# EconetTerminator.net
KiCad netlist of a schematic drawn in Altium Designer
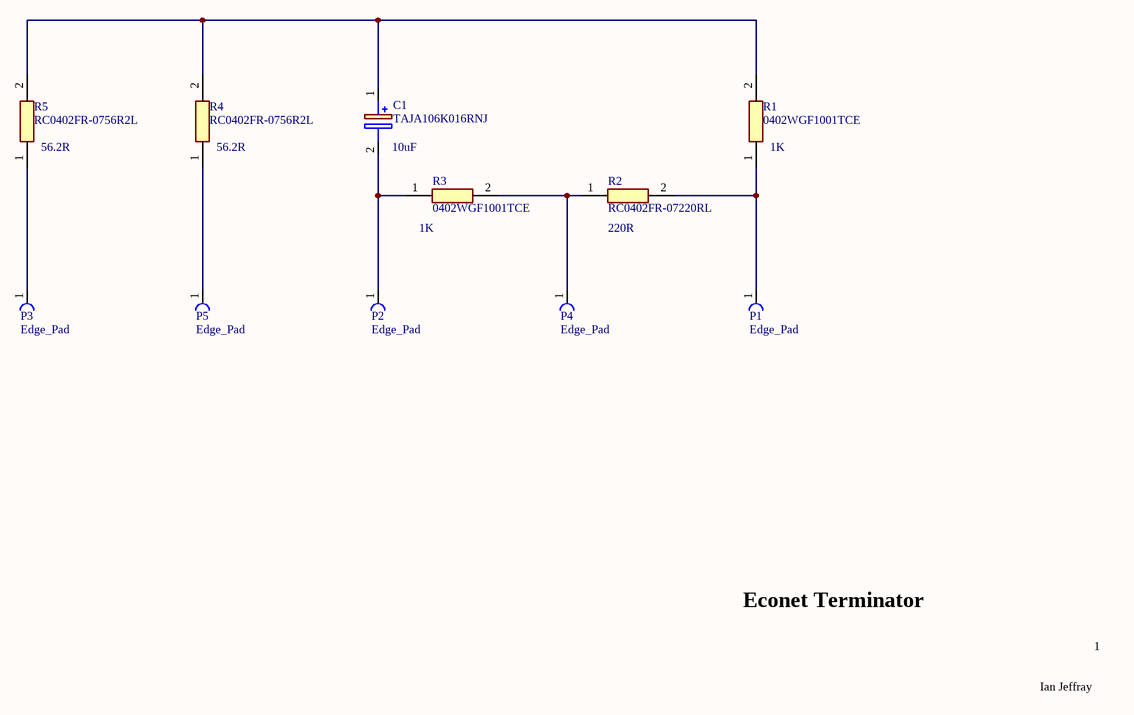
[diagram p0: EconetTerminator.SchDoc]

(export (version "E")
  (design (tool "Eeschema 10.0.6"))
  (components
    (comp (ref "C1")
      (value "TAJA106K016RNJ")
      (footprint "SamacSys:CAPPM3216X180N")
      (description "10uF Tantalum")
      (fields (field (name "MOUSER PART NUMBER") "581-TAJA106K016R") (field (name "ALTIUM_VALUE") "10uF"))
      (libsource (lib "*") (part "TAJA106K016RNJ"))
    )
    (comp (ref "P1")
      (value "Edge_Pad")
      (footprint "CONS_PAD")
      (description "Edge Pad")
      (libsource (lib "EconetTerminator") (part "Edge_Pad"))
    )
    (comp (ref "P2")
      (value "Edge_Pad")
      (footprint "CONS_PAD")
      (description "Edge Pad")
      (libsource (lib "EconetTerminator") (part "Edge_Pad"))
    )
    (comp (ref "P3")
      (value "Edge_Pad")
      (footprint "CONS_PAD")
      (description "Edge Pad")
      (libsource (lib "EconetTerminator") (part "Edge_Pad"))
    )
    (comp (ref "P4")
      (value "Edge_Pad")
      (footprint "CONS_PAD")
      (description "Edge Pad")
      (libsource (lib "EconetTerminator") (part "Edge_Pad"))
    )
    (comp (ref "P5")
      (value "Edge_Pad")
      (footprint "CONS_PAD")
      (description "Edge Pad")
      (libsource (lib "EconetTerminator") (part "Edge_Pad"))
    )
    (comp (ref "R1")
      (value "0402WGF1001TCE")
      (footprint "SamacSys:RESC1005X40N")
      (description "Resistor 1K")
      (fields (field (name "ALTIUM_VALUE") "1K"))
      (libsource (lib "") (part "0402WGF1001TCE_1"))
    )
    (comp (ref "R2")
      (value "RC0402FR-07220RL")
      (footprint "SamacSys:RESC1005X40N")
      (description "Resistor 220R")
      (fields (field (name "MOUSER PART NUMBER") "603-RC0402FR-07220RL") (field (name "ALTIUM_VALUE") "220R"))
      (libsource (lib "*") (part "RC0402FR-07220RL"))
    )
    (comp (ref "R3")
      (value "0402WGF1001TCE")
      (footprint "SamacSys:RESC1005X40N")
      (description "Resistor 1K")
      (fields (field (name "ALTIUM_VALUE") "1K"))
      (libsource (lib "*") (part "0402WGF1001TCE"))
    )
    (comp (ref "R4")
      (value "RC0402FR-0756R2L")
      (footprint "SamacSys:RESC1005X40N")
      (description "Resistor 56R2")
      (fields (field (name "ALTIUM_VALUE") "56.2R"))
      (libsource (lib "*") (part "RC0402FR-0756R2L"))
    )
    (comp (ref "R5")
      (value "RC0402FR-0756R2L")
      (footprint "SamacSys:RESC1005X40N")
      (description "Resistor 56R2")
      (fields (field (name "ALTIUM_VALUE") "56.2R"))
      (libsource (lib "*") (part "RC0402FR-0756R2L"))
    )
  )
  (nets
    (net (code "1") (name "Net-(C1-+)") (class "Default")
      (node (ref "C1") (pin "1") (pinfunction "+_1") (pintype "passive"))
      (node (ref "R1") (pin "2") (pinfunction "2_2") (pintype "passive"))
      (node (ref "R4") (pin "2") (pinfunction "2_2") (pintype "passive"))
      (node (ref "R5") (pin "2") (pinfunction "2_2") (pintype "passive"))
    )
    (net (code "2") (name "Net-(C1--)") (class "Default")
      (node (ref "C1") (pin "2") (pinfunction "-_2") (pintype "passive"))
      (node (ref "P2") (pin "1") (pinfunction "1_1") (pintype "passive"))
      (node (ref "R3") (pin "1") (pinfunction "1_1") (pintype "passive"))
    )
    (net (code "3") (name "Net-(P1-Pad1)") (class "Default")
      (node (ref "P1") (pin "1") (pinfunction "1_1") (pintype "passive"))
      (node (ref "R1") (pin "1") (pinfunction "1_1") (pintype "passive"))
      (node (ref "R2") (pin "2") (pinfunction "2_2") (pintype "passive"))
    )
    (net (code "4") (name "Net-(P3-Pad1)") (class "Default")
      (node (ref "P3") (pin "1") (pinfunction "1_1") (pintype "passive"))
      (node (ref "R5") (pin "1") (pinfunction "1_1") (pintype "passive"))
    )
    (net (code "5") (name "Net-(P4-Pad1)") (class "Default")
      (node (ref "P4") (pin "1") (pinfunction "1_1") (pintype "passive"))
      (node (ref "R2") (pin "1") (pinfunction "1_1") (pintype "passive"))
      (node (ref "R3") (pin "2") (pinfunction "2_2") (pintype "passive"))
    )
    (net (code "6") (name "Net-(P5-Pad1)") (class "Default")
      (node (ref "P5") (pin "1") (pinfunction "1_1") (pintype "passive"))
      (node (ref "R4") (pin "1") (pinfunction "1_1") (pintype "passive"))
    )
  )
)
